# pecl_pulse_driver_v2.net
KiCad netlist of a schematic drawn in EAGLE
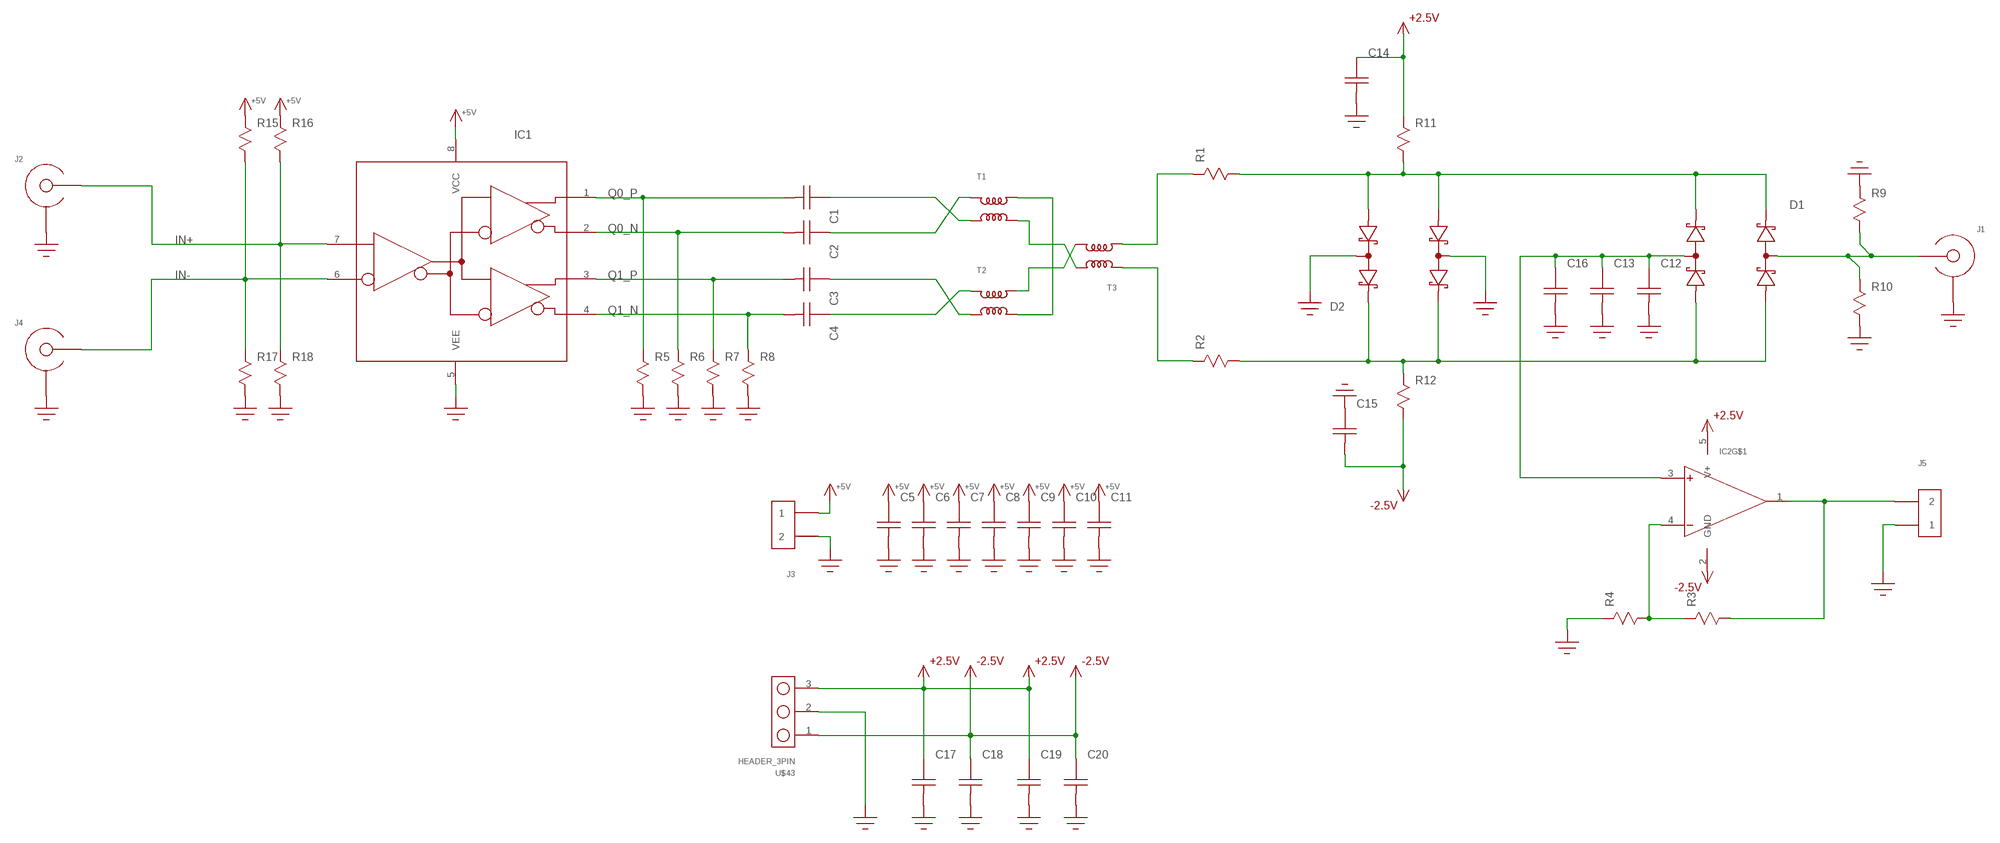
[diagram p0: schematic, sheet 1]

(export (version "E")
  (design (tool "Eeschema 10.0.6"))
  (components
    (comp (ref "C1") (value "C") (footprint "eagle-import:C0402") (libsource (lib "eagle-import") (part "C")))
    (comp (ref "C2") (value "C") (footprint "eagle-import:C0402") (libsource (lib "eagle-import") (part "C")))
    (comp (ref "C3") (value "C") (footprint "eagle-import:C0402") (libsource (lib "eagle-import") (part "C")))
    (comp (ref "C4") (value "C") (footprint "eagle-import:C0402") (libsource (lib "eagle-import") (part "C")))
    (comp (ref "C5")
      (value "C0603")
      (footprint "eagle-import:C0603")
      (libsource (lib "eagle-import") (part "C0603"))
    )
    (comp (ref "C6")
      (value "C0603")
      (footprint "eagle-import:C0603")
      (libsource (lib "eagle-import") (part "C0603"))
    )
    (comp (ref "C7")
      (value "C0805")
      (footprint "eagle-import:0805")
      (libsource (lib "eagle-import") (part "C0805"))
    )
    (comp (ref "C8")
      (value "C0603")
      (footprint "eagle-import:C0603")
      (libsource (lib "eagle-import") (part "C0603"))
    )
    (comp (ref "C9")
      (value "C0603")
      (footprint "eagle-import:C0603")
      (libsource (lib "eagle-import") (part "C0603"))
    )
    (comp (ref "C10")
      (value "C0603")
      (footprint "eagle-import:C0603")
      (libsource (lib "eagle-import") (part "C0603"))
    )
    (comp (ref "C11")
      (value "C0603")
      (footprint "eagle-import:C0603")
      (libsource (lib "eagle-import") (part "C0603"))
    )
    (comp (ref "C12")
      (value "C")
      (footprint "eagle-import:C0402")
      (libsource (lib "eagle-import") (part "C"))
    )
    (comp (ref "C13")
      (value "C")
      (footprint "eagle-import:C0402")
      (libsource (lib "eagle-import") (part "C"))
    )
    (comp (ref "C14")
      (value "C")
      (footprint "eagle-import:C0402")
      (libsource (lib "eagle-import") (part "C"))
    )
    (comp (ref "C15")
      (value "C")
      (footprint "eagle-import:C0402")
      (libsource (lib "eagle-import") (part "C"))
    )
    (comp (ref "C16")
      (value "C")
      (footprint "eagle-import:C0402")
      (libsource (lib "eagle-import") (part "C"))
    )
    (comp (ref "C17")
      (value "C0603")
      (footprint "eagle-import:C0603")
      (libsource (lib "eagle-import") (part "C0603"))
    )
    (comp (ref "C18")
      (value "C0603")
      (footprint "eagle-import:C0603")
      (libsource (lib "eagle-import") (part "C0603"))
    )
    (comp (ref "C19")
      (value "C0603")
      (footprint "eagle-import:C0603")
      (libsource (lib "eagle-import") (part "C0603"))
    )
    (comp (ref "C20")
      (value "C0603")
      (footprint "eagle-import:C0603")
      (libsource (lib "eagle-import") (part "C0603"))
    )
    (comp (ref "D1")
      (value "SMS3923-081")
      (footprint "eagle-import:SC-88")
      (libsource (lib "eagle-import") (part "SMS3923-081"))
    )
    (comp (ref "D2")
      (value "SMS3923-081")
      (footprint "eagle-import:SC-88")
      (libsource (lib "eagle-import") (part "SMS3923-081"))
    )
    (comp (ref "IC1")
      (value "SY10EP89V")
      (footprint "eagle-import:SOIC8")
      (libsource (lib "eagle-import") (part "SY10EP89V"))
    )
    (comp (ref "IC2")
      (value "MCP6V81")
      (footprint "eagle-import:SOT23-5")
      (libsource (lib "eagle-import") (part "MCP6V81"))
    )
    (comp (ref "J1")
      (value "SMA-EDGE-LAUNCH4L-4020-TAPER-FIXED")
      (footprint "eagle-import:SMA_EDGE_LAUNCH_4L_4020_TAPER_FIXED")
      (libsource (lib "eagle-import") (part "SMA-EDGE-LAUNCH4L-4020-TAPER-FIXED"))
    )
    (comp (ref "J2")
      (value "SMA-EDGE-LAUNCH4L-4020-TAPER-FIXED")
      (footprint "eagle-import:SMA_EDGE_LAUNCH_4L_4020_TAPER_FIXED")
      (libsource (lib "eagle-import") (part "SMA-EDGE-LAUNCH4L-4020-TAPER-FIXED"))
    )
    (comp (ref "J3")
      (value "HEADER_2PIN")
      (footprint "eagle-import:HEADER_2PIN")
      (libsource (lib "eagle-import") (part "HEADER_2PIN"))
    )
    (comp (ref "J4")
      (value "SMA-EDGE-LAUNCH4L-4020-TAPER-FIXED")
      (footprint "eagle-import:SMA_EDGE_LAUNCH_4L_4020_TAPER_FIXED")
      (libsource (lib "eagle-import") (part "SMA-EDGE-LAUNCH4L-4020-TAPER-FIXED"))
    )
    (comp (ref "J5")
      (value "HEADER_2PIN")
      (footprint "eagle-import:HEADER_2PIN")
      (libsource (lib "eagle-import") (part "HEADER_2PIN"))
    )
    (comp (ref "R1")
      (value "R0402")
      (footprint "eagle-import:0402")
      (libsource (lib "eagle-import") (part "R0402"))
    )
    (comp (ref "R2")
      (value "R0402")
      (footprint "eagle-import:0402")
      (libsource (lib "eagle-import") (part "R0402"))
    )
    (comp (ref "R3")
      (value "R0603")
      (footprint "eagle-import:R0603")
      (libsource (lib "eagle-import") (part "R0603"))
    )
    (comp (ref "R4")
      (value "R0603")
      (footprint "eagle-import:R0603")
      (libsource (lib "eagle-import") (part "R0603"))
    )
    (comp (ref "R5")
      (value "R0603")
      (footprint "eagle-import:R0603")
      (libsource (lib "eagle-import") (part "R0603"))
    )
    (comp (ref "R6")
      (value "R0603")
      (footprint "eagle-import:R0603")
      (libsource (lib "eagle-import") (part "R0603"))
    )
    (comp (ref "R7")
      (value "R0603")
      (footprint "eagle-import:R0603")
      (libsource (lib "eagle-import") (part "R0603"))
    )
    (comp (ref "R8")
      (value "R0603")
      (footprint "eagle-import:R0603")
      (libsource (lib "eagle-import") (part "R0603"))
    )
    (comp (ref "R9")
      (value "R0402")
      (footprint "eagle-import:0402")
      (libsource (lib "eagle-import") (part "R0402"))
    )
    (comp (ref "R10")
      (value "R0402")
      (footprint "eagle-import:0402")
      (libsource (lib "eagle-import") (part "R0402"))
    )
    (comp (ref "R11")
      (value "R0402")
      (footprint "eagle-import:0402")
      (libsource (lib "eagle-import") (part "R0402"))
    )
    (comp (ref "R12")
      (value "R0402")
      (footprint "eagle-import:0402")
      (libsource (lib "eagle-import") (part "R0402"))
    )
    (comp (ref "R15")
      (value "R0603")
      (footprint "eagle-import:R0603")
      (libsource (lib "eagle-import") (part "R0603"))
    )
    (comp (ref "R16")
      (value "R0603")
      (footprint "eagle-import:R0603")
      (libsource (lib "eagle-import") (part "R0603"))
    )
    (comp (ref "R17")
      (value "R0603")
      (footprint "eagle-import:R0603")
      (libsource (lib "eagle-import") (part "R0603"))
    )
    (comp (ref "R18")
      (value "R0603")
      (footprint "eagle-import:R0603")
      (libsource (lib "eagle-import") (part "R0603"))
    )
    (comp (ref "T1")
      (value "MABA007159")
      (footprint "eagle-import:MABAES0061")
      (libsource (lib "eagle-import") (part "MABA007159"))
    )
    (comp (ref "T2")
      (value "MABA007159")
      (footprint "eagle-import:MABAES0061")
      (libsource (lib "eagle-import") (part "MABA007159"))
    )
    (comp (ref "T3")
      (value "MABA007159")
      (footprint "eagle-import:MABAES0061")
      (libsource (lib "eagle-import") (part "MABA007159"))
    )
    (comp (ref "U$43")
      (value "HEADER_3PIN")
      (footprint "eagle-import:HEADER_3PIN")
      (libsource (lib "eagle-import") (part "HEADER_3PIN"))
    )
  )
  (nets
    (net (code "1") (name "+2.5V") (class "Default")
      (node (ref "C14") (pin "2") (pinfunction "P$2_2") (pintype "bidirectional"))
      (node (ref "C17") (pin "P$2") (pinfunction "P$2_P$2") (pintype "bidirectional"))
      (node (ref "C19") (pin "P$2") (pinfunction "P$2_P$2") (pintype "bidirectional"))
      (node (ref "IC2") (pin "5") (pinfunction "V+_5") (pintype "bidirectional"))
      (node (ref "R11") (pin "1") (pinfunction "P$3_1") (pintype "bidirectional"))
      (node (ref "U$43") (pin "3") (pinfunction "3_3") (pintype "bidirectional"))
    )
    (net (code "2") (name "+5V") (class "Default")
      (node (ref "C10") (pin "P$2") (pinfunction "P$2_P$2") (pintype "bidirectional"))
      (node (ref "C11") (pin "P$2") (pinfunction "P$2_P$2") (pintype "bidirectional"))
      (node (ref "C5") (pin "P$2") (pinfunction "P$2_P$2") (pintype "bidirectional"))
      (node (ref "C6") (pin "P$2") (pinfunction "P$2_P$2") (pintype "bidirectional"))
      (node (ref "C7") (pin "P$2") (pinfunction "P$2_P$2") (pintype "bidirectional"))
      (node (ref "C8") (pin "P$2") (pinfunction "P$2_P$2") (pintype "bidirectional"))
      (node (ref "C9") (pin "P$2") (pinfunction "P$2_P$2") (pintype "bidirectional"))
      (node (ref "IC1") (pin "8") (pinfunction "VCC_8") (pintype "bidirectional"))
      (node (ref "J3") (pin "1") (pinfunction "1_1") (pintype "bidirectional"))
      (node (ref "R15") (pin "P$1") (pinfunction "P$3_P$1") (pintype "bidirectional"))
      (node (ref "R16") (pin "P$1") (pinfunction "P$3_P$1") (pintype "bidirectional"))
    )
    (net (code "3") (name "-2.5V") (class "Default")
      (node (ref "C15") (pin "1") (pinfunction "P$1_1") (pintype "bidirectional"))
      (node (ref "C18") (pin "P$2") (pinfunction "P$2_P$2") (pintype "bidirectional"))
      (node (ref "C20") (pin "P$2") (pinfunction "P$2_P$2") (pintype "bidirectional"))
      (node (ref "IC2") (pin "2") (pinfunction "GND_2") (pintype "bidirectional"))
      (node (ref "R12") (pin "2") (pinfunction "P$4_2") (pintype "bidirectional"))
      (node (ref "U$43") (pin "1") (pinfunction "1_1") (pintype "bidirectional"))
    )
    (net (code "4") (name "/IN+") (class "Default")
      (node (ref "IC1") (pin "7") (pinfunction "D_7") (pintype "bidirectional"))
      (node (ref "J2") (pin "CENTER@1") (pinfunction "CENTER_CENTER@1") (pintype "bidirectional"))
      (node (ref "J2") (pin "P$3") (pinfunction "CENTER_P$3") (pintype "bidirectional"))
      (node (ref "R16") (pin "P$2") (pinfunction "P$4_P$2") (pintype "bidirectional"))
      (node (ref "R18") (pin "P$1") (pinfunction "P$3_P$1") (pintype "bidirectional"))
    )
    (net (code "5") (name "/IN-") (class "Default")
      (node (ref "IC1") (pin "6") (pinfunction "~{D}_6") (pintype "bidirectional"))
      (node (ref "J4") (pin "CENTER@1") (pinfunction "CENTER_CENTER@1") (pintype "bidirectional"))
      (node (ref "J4") (pin "P$3") (pinfunction "CENTER_P$3") (pintype "bidirectional"))
      (node (ref "R15") (pin "P$2") (pinfunction "P$4_P$2") (pintype "bidirectional"))
      (node (ref "R17") (pin "P$1") (pinfunction "P$3_P$1") (pintype "bidirectional"))
    )
    (net (code "6") (name "/Q0_N") (class "Default")
      (node (ref "C2") (pin "1") (pinfunction "P$1_1") (pintype "bidirectional"))
      (node (ref "IC1") (pin "2") (pinfunction "~{Q0}_2") (pintype "bidirectional"))
      (node (ref "R6") (pin "P$1") (pinfunction "P$3_P$1") (pintype "bidirectional"))
    )
    (net (code "7") (name "/Q0_P") (class "Default")
      (node (ref "C1") (pin "1") (pinfunction "P$1_1") (pintype "bidirectional"))
      (node (ref "IC1") (pin "1") (pinfunction "Q0_1") (pintype "bidirectional"))
      (node (ref "R5") (pin "P$1") (pinfunction "P$3_P$1") (pintype "bidirectional"))
    )
    (net (code "8") (name "/Q1_N") (class "Default")
      (node (ref "C4") (pin "1") (pinfunction "P$1_1") (pintype "bidirectional"))
      (node (ref "IC1") (pin "4") (pinfunction "~{Q1}_4") (pintype "bidirectional"))
      (node (ref "R8") (pin "P$1") (pinfunction "P$3_P$1") (pintype "bidirectional"))
    )
    (net (code "9") (name "/Q1_P") (class "Default")
      (node (ref "C3") (pin "1") (pinfunction "P$1_1") (pintype "bidirectional"))
      (node (ref "IC1") (pin "3") (pinfunction "Q1_3") (pintype "bidirectional"))
      (node (ref "R7") (pin "P$1") (pinfunction "P$3_P$1") (pintype "bidirectional"))
    )
    (net (code "10") (name "GND") (class "Default")
      (node (ref "C10") (pin "P$1") (pinfunction "P$1_P$1") (pintype "bidirectional"))
      (node (ref "C11") (pin "P$1") (pinfunction "P$1_P$1") (pintype "bidirectional"))
      (node (ref "C12") (pin "1") (pinfunction "P$1_1") (pintype "bidirectional"))
      (node (ref "C13") (pin "1") (pinfunction "P$1_1") (pintype "bidirectional"))
      (node (ref "C14") (pin "1") (pinfunction "P$1_1") (pintype "bidirectional"))
      (node (ref "C15") (pin "2") (pinfunction "P$2_2") (pintype "bidirectional"))
      (node (ref "C16") (pin "1") (pinfunction "P$1_1") (pintype "bidirectional"))
      (node (ref "C17") (pin "P$1") (pinfunction "P$1_P$1") (pintype "bidirectional"))
      (node (ref "C18") (pin "P$1") (pinfunction "P$1_P$1") (pintype "bidirectional"))
      (node (ref "C19") (pin "P$1") (pinfunction "P$1_P$1") (pintype "bidirectional"))
      (node (ref "C20") (pin "P$1") (pinfunction "P$1_P$1") (pintype "bidirectional"))
      (node (ref "C5") (pin "P$1") (pinfunction "P$1_P$1") (pintype "bidirectional"))
      (node (ref "C6") (pin "P$1") (pinfunction "P$1_P$1") (pintype "bidirectional"))
      (node (ref "C7") (pin "P$1") (pinfunction "P$1_P$1") (pintype "bidirectional"))
      (node (ref "C8") (pin "P$1") (pinfunction "P$1_P$1") (pintype "bidirectional"))
      (node (ref "C9") (pin "P$1") (pinfunction "P$1_P$1") (pintype "bidirectional"))
      (node (ref "D2") (pin "2") (pinfunction "COMMON0_2") (pintype "bidirectional"))
      (node (ref "D2") (pin "5") (pinfunction "COMMON1_5") (pintype "bidirectional"))
      (node (ref "IC1") (pin "5") (pinfunction "VEE_5") (pintype "bidirectional"))
      (node (ref "J1") (pin "BOTTOM_GND") (pinfunction "SHIELD_BOTTOM_GND") (pintype "bidirectional"))
      (node (ref "J1") (pin "GND@1") (pinfunction "SHIELD_GND@1") (pintype "bidirectional"))
      (node (ref "J1") (pin "GND@14") (pinfunction "SHIELD_GND@14") (pintype "bidirectional"))
      (node (ref "J1") (pin "GND@15") (pinfunction "SHIELD_GND@15") (pintype "bidirectional"))
      (node (ref "J1") (pin "GND@16") (pinfunction "SHIELD_GND@16") (pintype "bidirectional"))
      (node (ref "J1") (pin "GND@17") (pinfunction "SHIELD_GND@17") (pintype "bidirectional"))
      (node (ref "J1") (pin "GND@2") (pinfunction "SHIELD_GND@2") (pintype "bidirectional"))
      (node (ref "J1") (pin "GND@3") (pinfunction "SHIELD_GND@3") (pintype "bidirectional"))
      (node (ref "J1") (pin "GND@4") (pinfunction "SHIELD_GND@4") (pintype "bidirectional"))
      (node (ref "J1") (pin "GND@5") (pinfunction "SHIELD_GND@5") (pintype "bidirectional"))
      (node (ref "J1") (pin "GND@6") (pinfunction "SHIELD_GND@6") (pintype "bidirectional"))
      (node (ref "J1") (pin "GND@7") (pinfunction "SHIELD_GND@7") (pintype "bidirectional"))
      (node (ref "J1") (pin "GND@8") (pinfunction "SHIELD_GND@8") (pintype "bidirectional"))
      (node (ref "J1") (pin "GND_PAD1") (pinfunction "SHIELD_GND_PAD1") (pintype "bidirectional"))
      (node (ref "J1") (pin "GND_PAD2") (pinfunction "SHIELD_GND_PAD2") (pintype "bidirectional"))
      (node (ref "J1") (pin "P$1") (pinfunction "SHIELD_P$1") (pintype "bidirectional"))
      (node (ref "J1") (pin "P$2") (pinfunction "SHIELD_P$2") (pintype "bidirectional"))
      (node (ref "J2") (pin "BOTTOM_GND") (pinfunction "SHIELD_BOTTOM_GND") (pintype "bidirectional"))
      (node (ref "J2") (pin "GND@1") (pinfunction "SHIELD_GND@1") (pintype "bidirectional"))
      (node (ref "J2") (pin "GND@14") (pinfunction "SHIELD_GND@14") (pintype "bidirectional"))
      (node (ref "J2") (pin "GND@15") (pinfunction "SHIELD_GND@15") (pintype "bidirectional"))
      (node (ref "J2") (pin "GND@16") (pinfunction "SHIELD_GND@16") (pintype "bidirectional"))
      (node (ref "J2") (pin "GND@17") (pinfunction "SHIELD_GND@17") (pintype "bidirectional"))
      (node (ref "J2") (pin "GND@2") (pinfunction "SHIELD_GND@2") (pintype "bidirectional"))
      (node (ref "J2") (pin "GND@3") (pinfunction "SHIELD_GND@3") (pintype "bidirectional"))
      (node (ref "J2") (pin "GND@4") (pinfunction "SHIELD_GND@4") (pintype "bidirectional"))
      (node (ref "J2") (pin "GND@5") (pinfunction "SHIELD_GND@5") (pintype "bidirectional"))
      (node (ref "J2") (pin "GND@6") (pinfunction "SHIELD_GND@6") (pintype "bidirectional"))
      (node (ref "J2") (pin "GND@7") (pinfunction "SHIELD_GND@7") (pintype "bidirectional"))
      (node (ref "J2") (pin "GND@8") (pinfunction "SHIELD_GND@8") (pintype "bidirectional"))
      (node (ref "J2") (pin "GND_PAD1") (pinfunction "SHIELD_GND_PAD1") (pintype "bidirectional"))
      (node (ref "J2") (pin "GND_PAD2") (pinfunction "SHIELD_GND_PAD2") (pintype "bidirectional"))
      (node (ref "J2") (pin "P$1") (pinfunction "SHIELD_P$1") (pintype "bidirectional"))
      (node (ref "J2") (pin "P$2") (pinfunction "SHIELD_P$2") (pintype "bidirectional"))
      (node (ref "J3") (pin "2") (pinfunction "2_2") (pintype "bidirectional"))
      (node (ref "J4") (pin "BOTTOM_GND") (pinfunction "SHIELD_BOTTOM_GND") (pintype "bidirectional"))
      (node (ref "J4") (pin "GND@1") (pinfunction "SHIELD_GND@1") (pintype "bidirectional"))
      (node (ref "J4") (pin "GND@14") (pinfunction "SHIELD_GND@14") (pintype "bidirectional"))
      (node (ref "J4") (pin "GND@15") (pinfunction "SHIELD_GND@15") (pintype "bidirectional"))
      (node (ref "J4") (pin "GND@16") (pinfunction "SHIELD_GND@16") (pintype "bidirectional"))
      (node (ref "J4") (pin "GND@17") (pinfunction "SHIELD_GND@17") (pintype "bidirectional"))
      (node (ref "J4") (pin "GND@2") (pinfunction "SHIELD_GND@2") (pintype "bidirectional"))
      (node (ref "J4") (pin "GND@3") (pinfunction "SHIELD_GND@3") (pintype "bidirectional"))
      (node (ref "J4") (pin "GND@4") (pinfunction "SHIELD_GND@4") (pintype "bidirectional"))
      (node (ref "J4") (pin "GND@5") (pinfunction "SHIELD_GND@5") (pintype "bidirectional"))
      (node (ref "J4") (pin "GND@6") (pinfunction "SHIELD_GND@6") (pintype "bidirectional"))
      (node (ref "J4") (pin "GND@7") (pinfunction "SHIELD_GND@7") (pintype "bidirectional"))
      (node (ref "J4") (pin "GND@8") (pinfunction "SHIELD_GND@8") (pintype "bidirectional"))
      (node (ref "J4") (pin "GND_PAD1") (pinfunction "SHIELD_GND_PAD1") (pintype "bidirectional"))
      (node (ref "J4") (pin "GND_PAD2") (pinfunction "SHIELD_GND_PAD2") (pintype "bidirectional"))
      (node (ref "J4") (pin "P$1") (pinfunction "SHIELD_P$1") (pintype "bidirectional"))
      (node (ref "J4") (pin "P$2") (pinfunction "SHIELD_P$2") (pintype "bidirectional"))
      (node (ref "J5") (pin "1") (pinfunction "1_1") (pintype "bidirectional"))
      (node (ref "R10") (pin "2") (pinfunction "P$4_2") (pintype "bidirectional"))
      (node (ref "R17") (pin "P$2") (pinfunction "P$4_P$2") (pintype "bidirectional"))
      (node (ref "R18") (pin "P$2") (pinfunction "P$4_P$2") (pintype "bidirectional"))
      (node (ref "R4") (pin "P$1") (pinfunction "P$3_P$1") (pintype "bidirectional"))
      (node (ref "R5") (pin "P$2") (pinfunction "P$4_P$2") (pintype "bidirectional"))
      (node (ref "R6") (pin "P$2") (pinfunction "P$4_P$2") (pintype "bidirectional"))
      (node (ref "R7") (pin "P$2") (pinfunction "P$4_P$2") (pintype "bidirectional"))
      (node (ref "R8") (pin "P$2") (pinfunction "P$4_P$2") (pintype "bidirectional"))
      (node (ref "R9") (pin "1") (pinfunction "P$3_1") (pintype "bidirectional"))
      (node (ref "U$43") (pin "2") (pinfunction "2_2") (pintype "bidirectional"))
    )
    (net (code "11") (name "Net-(C1-P$2)") (class "Default")
      (node (ref "C1") (pin "2") (pinfunction "P$2_2") (pintype "bidirectional"))
      (node (ref "T1") (pin "4") (pinfunction "4_4") (pintype "bidirectional"))
    )
    (net (code "12") (name "Net-(C2-P$2)") (class "Default")
      (node (ref "C2") (pin "2") (pinfunction "P$2_2") (pintype "bidirectional"))
      (node (ref "T1") (pin "5") (pinfunction "5_5") (pintype "bidirectional"))
    )
    (net (code "13") (name "Net-(C3-P$2)") (class "Default")
      (node (ref "C3") (pin "2") (pinfunction "P$2_2") (pintype "bidirectional"))
      (node (ref "T2") (pin "4") (pinfunction "4_4") (pintype "bidirectional"))
    )
    (net (code "14") (name "Net-(C4-P$2)") (class "Default")
      (node (ref "C4") (pin "2") (pinfunction "P$2_2") (pintype "bidirectional"))
      (node (ref "T2") (pin "5") (pinfunction "5_5") (pintype "bidirectional"))
    )
    (net (code "15") (name "Net-(C12-P$2)") (class "Default")
      (node (ref "C12") (pin "2") (pinfunction "P$2_2") (pintype "bidirectional"))
      (node (ref "C13") (pin "2") (pinfunction "P$2_2") (pintype "bidirectional"))
      (node (ref "C16") (pin "2") (pinfunction "P$2_2") (pintype "bidirectional"))
      (node (ref "D1") (pin "5") (pinfunction "COMMON1_5") (pintype "bidirectional"))
      (node (ref "IC2") (pin "3") (pinfunction "+_3") (pintype "bidirectional"))
    )
    (net (code "16") (name "Net-(D1-ANODE0)") (class "Default")
      (node (ref "D1") (pin "1") (pinfunction "ANODE0_1") (pintype "bidirectional"))
      (node (ref "D1") (pin "6") (pinfunction "ANODE1_6") (pintype "bidirectional"))
      (node (ref "D2") (pin "3") (pinfunction "CATHODE0_3") (pintype "bidirectional"))
      (node (ref "D2") (pin "4") (pinfunction "CATHODE1_4") (pintype "bidirectional"))
      (node (ref "R12") (pin "1") (pinfunction "P$3_1") (pintype "bidirectional"))
      (node (ref "R2") (pin "2") (pinfunction "P$4_2") (pintype "bidirectional"))
    )
    (net (code "17") (name "Net-(D1-CATHODE0)") (class "Default")
      (node (ref "D1") (pin "3") (pinfunction "CATHODE0_3") (pintype "bidirectional"))
      (node (ref "D1") (pin "4") (pinfunction "CATHODE1_4") (pintype "bidirectional"))
      (node (ref "D2") (pin "1") (pinfunction "ANODE0_1") (pintype "bidirectional"))
      (node (ref "D2") (pin "6") (pinfunction "ANODE1_6") (pintype "bidirectional"))
      (node (ref "R1") (pin "2") (pinfunction "P$4_2") (pintype "bidirectional"))
      (node (ref "R11") (pin "2") (pinfunction "P$4_2") (pintype "bidirectional"))
    )
    (net (code "18") (name "Net-(D1-COMMON0)") (class "Default")
      (node (ref "D1") (pin "2") (pinfunction "COMMON0_2") (pintype "bidirectional"))
      (node (ref "J1") (pin "CENTER@1") (pinfunction "CENTER_CENTER@1") (pintype "bidirectional"))
      (node (ref "J1") (pin "P$3") (pinfunction "CENTER_P$3") (pintype "bidirectional"))
      (node (ref "R10") (pin "1") (pinfunction "P$3_1") (pintype "bidirectional"))
      (node (ref "R9") (pin "2") (pinfunction "P$4_2") (pintype "bidirectional"))
    )
    (net (code "19") (name "Net-(IC2A--)") (class "Default")
      (node (ref "IC2") (pin "4") (pinfunction "-_4") (pintype "bidirectional"))
      (node (ref "R3") (pin "P$1") (pinfunction "P$3_P$1") (pintype "bidirectional"))
      (node (ref "R4") (pin "P$2") (pinfunction "P$4_P$2") (pintype "bidirectional"))
    )
    (net (code "20") (name "Net-(IC2A-OUT)") (class "Default")
      (node (ref "IC2") (pin "1") (pinfunction "OUT_1") (pintype "bidirectional"))
      (node (ref "J5") (pin "2") (pinfunction "2_2") (pintype "bidirectional"))
      (node (ref "R3") (pin "P$2") (pinfunction "P$4_P$2") (pintype "bidirectional"))
    )
    (net (code "21") (name "Net-(R1-P$3)") (class "Default")
      (node (ref "R1") (pin "1") (pinfunction "P$3_1") (pintype "bidirectional"))
      (node (ref "T3") (pin "4") (pinfunction "4_4") (pintype "bidirectional"))
    )
    (net (code "22") (name "Net-(R2-P$3)") (class "Default")
      (node (ref "R2") (pin "1") (pinfunction "P$3_1") (pintype "bidirectional"))
      (node (ref "T3") (pin "5") (pinfunction "5_5") (pintype "bidirectional"))
    )
    (net (code "23") (name "Net-(T1-Pad1)") (class "Default")
      (node (ref "T1") (pin "1") (pinfunction "1_1") (pintype "bidirectional"))
      (node (ref "T2") (pin "3") (pinfunction "3_3") (pintype "bidirectional"))
    )
    (net (code "24") (name "Net-(T1-Pad3)") (class "Default")
      (node (ref "T1") (pin "3") (pinfunction "3_3") (pintype "bidirectional"))
      (node (ref "T3") (pin "1") (pinfunction "1_1") (pintype "bidirectional"))
    )
    (net (code "25") (name "Net-(T2-Pad1)") (class "Default")
      (node (ref "T2") (pin "1") (pinfunction "1_1") (pintype "bidirectional"))
      (node (ref "T3") (pin "3") (pinfunction "3_3") (pintype "bidirectional"))
    )
  )
)
